# Simple-Bug-BC547.net
KiCad netlist of a schematic drawn in EAGLE
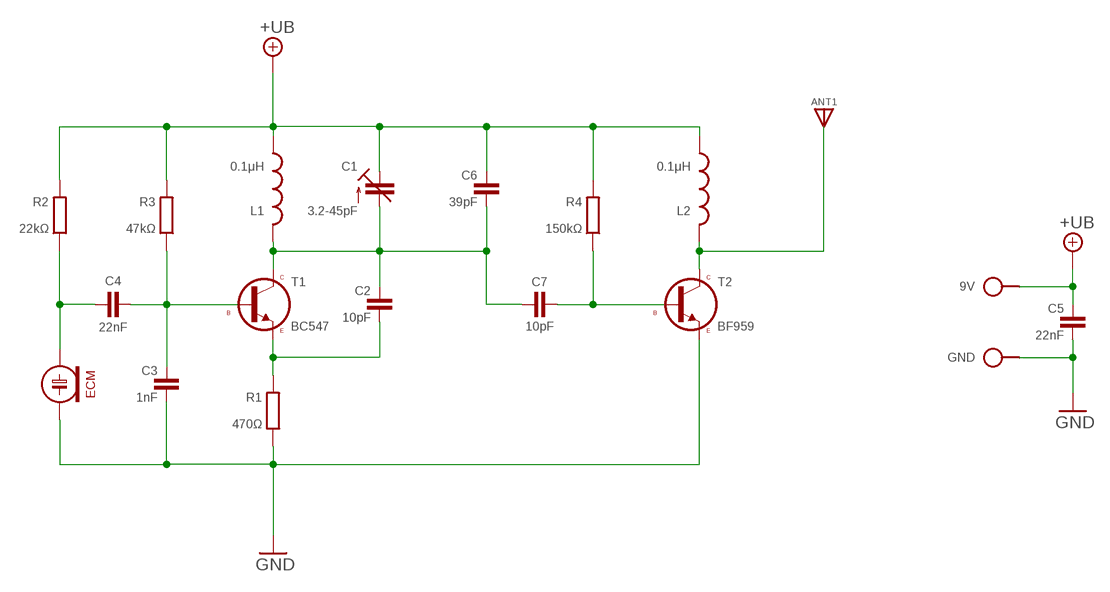
[diagram p0: schematic, sheet 1]

(export (version "E")
  (design (tool "Eeschema 10.0.6"))
  (components
    (comp (ref "9V")
      (value "SPAD")
      (footprint "eagle-import:SPAD@1")
      (libsource (lib "eagle-import") (part "SPAD"))
    )
    (comp (ref "ANT1")
      (value "ANT")
      (footprint "eagle-import:SPAD")
      (libsource (lib "eagle-import") (part "ANT"))
    )
    (comp (ref "C1")
      (value "3.2-45pF")
      (footprint "eagle-import:TRIM-2222-808")
      (libsource (lib "eagle-import") (part "C-TR-PH201272222-808-2PIN"))
    )
    (comp (ref "C2")
      (value "10pF")
      (footprint "eagle-import:C025-015X024")
      (libsource (lib "eagle-import") (part "C025-015X024"))
    )
    (comp (ref "C3")
      (value "1nF")
      (footprint "eagle-import:C025-020X036")
      (libsource (lib "eagle-import") (part "C025-020X036"))
    )
    (comp (ref "C4")
      (value "22nF")
      (footprint "eagle-import:C050-020X044")
      (libsource (lib "eagle-import") (part "C050-020X044"))
    )
    (comp (ref "C5")
      (value "22nF")
      (footprint "eagle-import:C050-020X036_V")
      (libsource (lib "eagle-import") (part "C050-020X036/V"))
    )
    (comp (ref "C6")
      (value "39pF")
      (footprint "eagle-import:C025-015X024")
      (libsource (lib "eagle-import") (part "C025-015X024"))
    )
    (comp (ref "C7")
      (value "10pF")
      (footprint "eagle-import:C025-015X024")
      (libsource (lib "eagle-import") (part "C-H025-015X024"))
    )
    (comp (ref "ECM")
      (value "ECM-5")
      (footprint "eagle-import:ECM-5")
      (libsource (lib "eagle-import") (part "ECM-5"))
    )
    (comp (ref "GND")
      (value "SPAD")
      (footprint "eagle-import:SPAD@1")
      (libsource (lib "eagle-import") (part "SPAD"))
    )
    (comp (ref "L1")
      (value "0.1μH")
      (footprint "eagle-import:L-08-10_5")
      (libsource (lib "eagle-import") (part "L08-10/5"))
    )
    (comp (ref "L2")
      (value "0.1μH")
      (footprint "eagle-import:L-08-10_5")
      (libsource (lib "eagle-import") (part "L08-10/5"))
    )
    (comp (ref "R1")
      (value "470Ω")
      (footprint "eagle-import:0204_10")
      (libsource (lib "eagle-import") (part "R0204/10"))
    )
    (comp (ref "R2")
      (value "22kΩ")
      (footprint "eagle-import:0204_10-V")
      (libsource (lib "eagle-import") (part "R0204/10-V"))
    )
    (comp (ref "R3")
      (value "47kΩ")
      (footprint "eagle-import:0204_10-V")
      (libsource (lib "eagle-import") (part "R0204/10-V"))
    )
    (comp (ref "R4")
      (value "150kΩ")
      (footprint "eagle-import:0204_10-V")
      (libsource (lib "eagle-import") (part "R0204/10-V"))
    )
    (comp (ref "T1")
      (value "BC547")
      (footprint "eagle-import:TO92")
      (libsource (lib "eagle-import") (part "BC547"))
    )
    (comp (ref "T2")
      (value "BF959")
      (footprint "eagle-import:TO92-CEB")
      (libsource (lib "eagle-import") (part "BF959"))
    )
  )
  (nets
    (net (code "1") (name "+UB") (class "Default")
      (node (ref "9V") (pin "1") (pinfunction "P$1_1") (pintype "passive"))
      (node (ref "C1") (pin "2") (pinfunction "E_2") (pintype "passive"))
      (node (ref "C5") (pin "1") (pinfunction "1_1") (pintype "passive"))
      (node (ref "C6") (pin "1") (pinfunction "1_1") (pintype "passive"))
      (node (ref "L1") (pin "2") (pinfunction "2_2") (pintype "passive"))
      (node (ref "L2") (pin "2") (pinfunction "2_2") (pintype "passive"))
      (node (ref "R2") (pin "1") (pinfunction "2_1") (pintype "passive"))
      (node (ref "R3") (pin "1") (pinfunction "2_1") (pintype "passive"))
      (node (ref "R4") (pin "1") (pinfunction "2_1") (pintype "passive"))
    )
    (net (code "2") (name "GND") (class "Default")
      (node (ref "C3") (pin "2") (pinfunction "2_2") (pintype "passive"))
      (node (ref "C5") (pin "2") (pinfunction "2_2") (pintype "passive"))
      (node (ref "ECM") (pin "2") (pinfunction "-_2") (pintype "passive"))
      (node (ref "GND") (pin "1") (pinfunction "P$1_1") (pintype "passive"))
      (node (ref "R1") (pin "2") (pinfunction "1_2") (pintype "passive"))
      (node (ref "T2") (pin "E") (pinfunction "E_E") (pintype "passive"))
    )
    (net (code "3") (name "Net-(ANT1-Pad1)") (class "Default")
      (node (ref "ANT1") (pin "1") (pinfunction "1_1") (pintype "output"))
      (node (ref "L2") (pin "1") (pinfunction "1_1") (pintype "passive"))
      (node (ref "T2") (pin "C") (pinfunction "C_C") (pintype "passive"))
    )
    (net (code "4") (name "Net-(C1-A)") (class "Default")
      (node (ref "C1") (pin "1") (pinfunction "A_1") (pintype "passive"))
      (node (ref "C2") (pin "1") (pinfunction "1_1") (pintype "passive"))
      (node (ref "C6") (pin "2") (pinfunction "2_2") (pintype "passive"))
      (node (ref "C7") (pin "1") (pinfunction "1_1") (pintype "passive"))
      (node (ref "L1") (pin "1") (pinfunction "1_1") (pintype "passive"))
      (node (ref "T1") (pin "1") (pinfunction "C_1") (pintype "passive"))
    )
    (net (code "5") (name "Net-(ECM-+)") (class "Default")
      (node (ref "C4") (pin "1") (pinfunction "1_1") (pintype "passive"))
      (node (ref "ECM") (pin "1") (pinfunction "+_1") (pintype "passive"))
      (node (ref "R2") (pin "2") (pinfunction "1_2") (pintype "passive"))
    )
    (net (code "6") (name "Net-(R1-2)") (class "Default")
      (node (ref "C2") (pin "2") (pinfunction "2_2") (pintype "passive"))
      (node (ref "R1") (pin "1") (pinfunction "2_1") (pintype "passive"))
      (node (ref "T1") (pin "3") (pinfunction "E_3") (pintype "passive"))
    )
    (net (code "7") (name "Net-(R3-1)") (class "Default")
      (node (ref "C3") (pin "1") (pinfunction "1_1") (pintype "passive"))
      (node (ref "C4") (pin "2") (pinfunction "2_2") (pintype "passive"))
      (node (ref "R3") (pin "2") (pinfunction "1_2") (pintype "passive"))
      (node (ref "T1") (pin "2") (pinfunction "B_2") (pintype "passive"))
    )
    (net (code "8") (name "Net-(R4-1)") (class "Default")
      (node (ref "C7") (pin "2") (pinfunction "2_2") (pintype "passive"))
      (node (ref "R4") (pin "2") (pinfunction "1_2") (pintype "passive"))
      (node (ref "T2") (pin "B") (pinfunction "B_B") (pintype "passive"))
    )
  )
)
